# ctrl.net
KiCad netlist of a schematic drawn in EAGLE
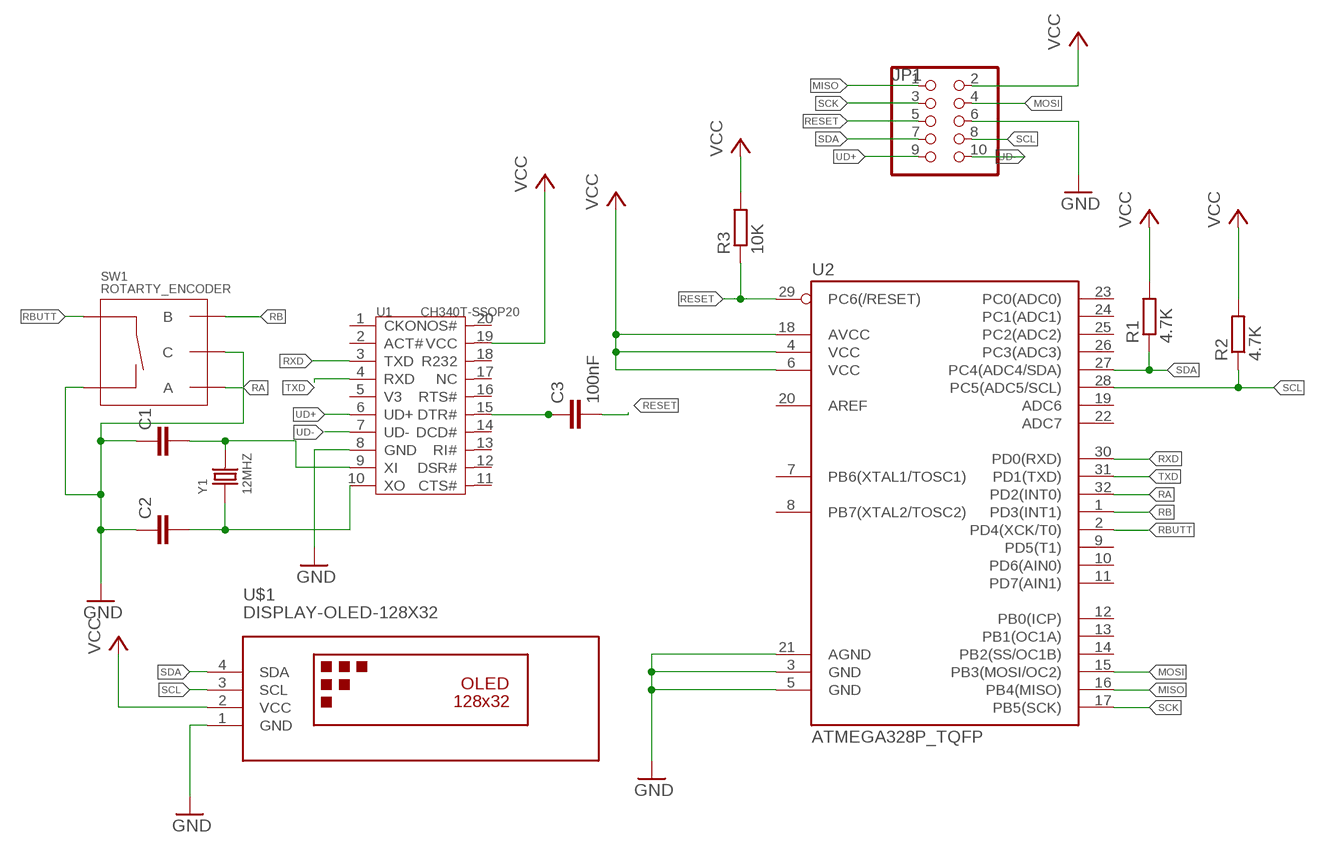
[diagram p0: schematic, sheet 1]

(export (version "E")
  (design (tool "Eeschema 10.0.6"))
  (components
    (comp (ref "C1")
      (value "C-EUC0805")
      (footprint "eagle-import:C0805")
      (libsource (lib "eagle-import") (part "C-EUC0805"))
    )
    (comp (ref "C2")
      (value "C-EUC0805")
      (footprint "eagle-import:C0805")
      (libsource (lib "eagle-import") (part "C-EUC0805"))
    )
    (comp (ref "C3")
      (value "100nF")
      (footprint "eagle-import:C0805")
      (libsource (lib "eagle-import") (part "C-EUC0805"))
    )
    (comp (ref "JP1")
      (value "PINHD-2X5")
      (footprint "eagle-import:2X05")
      (libsource (lib "eagle-import") (part "PINHD-2X5"))
    )
    (comp (ref "R1")
      (value "4.7K")
      (footprint "eagle-import:M0805")
      (libsource (lib "eagle-import") (part "R-EU_M0805"))
    )
    (comp (ref "R2")
      (value "4.7K")
      (footprint "eagle-import:M0805")
      (libsource (lib "eagle-import") (part "R-EU_M0805"))
    )
    (comp (ref "R3")
      (value "10K")
      (footprint "eagle-import:M0805")
      (libsource (lib "eagle-import") (part "R-EU_M0805"))
    )
    (comp (ref "SW1")
      (value "ROTARTY_ENCODER")
      (footprint "eagle-import:ROTARY_ENC_PLAIN")
      (libsource (lib "eagle-import") (part "ROTARTY_ENCODER"))
    )
    (comp (ref "U$1")
      (value "DISPLAY-OLED-128X32")
      (footprint "eagle-import:DISPLAY-OLED-128X32")
      (libsource (lib "eagle-import") (part "DISPLAY-OLED-128X32"))
    )
    (comp (ref "U1")
      (value "CH340T-SSOP20")
      (footprint "eagle-import:SSOP20-0.65-7.6X5.2MM")
      (fields (field (name "MPN") "CH340T"))
      (libsource (lib "eagle-import") (part "INTERFACE-CH340T(SSOP20)"))
    )
    (comp (ref "U2")
      (value "ATMEGA328P_TQFP")
      (footprint "eagle-import:TQFP32-08")
      (libsource (lib "eagle-import") (part "ATMEGA328P_TQFP"))
    )
    (comp (ref "Y1")
      (value "12MHZ")
      (footprint "eagle-import:X2-SMD-5.0X3.2X1.3MM")
      (fields (field (name "MPN") "5032/2P"))
      (libsource (lib "eagle-import") (part "SMD-CRYSTAL-12MHZ-20PF-20PPM-40R(2P-5.0X3.2MM)"))
    )
  )
  (nets
    (net (code "1") (name "/NOS#") (class "Default")
      (node (ref "U1") (pin "20") (pinfunction "NOS#_20") (pintype "power_in"))
    )
    (net (code "2") (name "/V3") (class "Default")
      (node (ref "U1") (pin "5") (pinfunction "V3_5") (pintype "power_in"))
    )
    (net (code "3") (name "GND") (class "Default")
      (node (ref "C1") (pin "1") (pinfunction "1_1") (pintype "passive"))
      (node (ref "C2") (pin "1") (pinfunction "1_1") (pintype "passive"))
      (node (ref "JP1") (pin "6") (pinfunction "6_6") (pintype "passive"))
      (node (ref "SW1") (pin "C") (pinfunction "C_C") (pintype "bidirectional"))
      (node (ref "SW1") (pin "SW-") (pinfunction "SW-_SW-") (pintype "bidirectional"))
      (node (ref "U$1") (pin "1") (pinfunction "GND_1") (pintype "power_in"))
      (node (ref "U1") (pin "8") (pinfunction "GND_8") (pintype "power_in"))
      (node (ref "U2") (pin "21") (pinfunction "AGND_21") (pintype "bidirectional"))
      (node (ref "U2") (pin "3") (pinfunction "GND_3") (pintype "bidirectional"))
      (node (ref "U2") (pin "5") (pinfunction "GND_5") (pintype "bidirectional"))
    )
    (net (code "4") (name "MISO") (class "Default")
      (node (ref "JP1") (pin "1") (pinfunction "1_1") (pintype "passive"))
      (node (ref "U2") (pin "16") (pinfunction "PB4(MISO)_16") (pintype "bidirectional"))
    )
    (net (code "5") (name "MOSI") (class "Default")
      (node (ref "JP1") (pin "4") (pinfunction "4_4") (pintype "passive"))
      (node (ref "U2") (pin "15") (pinfunction "PB3(MOSI/OC2)_15") (pintype "bidirectional"))
    )
    (net (code "6") (name "Net-(U1-DTR#)") (class "Default")
      (node (ref "C3") (pin "1") (pinfunction "1_1") (pintype "passive"))
      (node (ref "U1") (pin "15") (pinfunction "DTR#_15") (pintype "output"))
    )
    (net (code "7") (name "Net-(U1-XI)") (class "Default")
      (node (ref "C1") (pin "2") (pinfunction "2_2") (pintype "passive"))
      (node (ref "U1") (pin "9") (pinfunction "XI_9") (pintype "input"))
      (node (ref "Y1") (pin "2") (pinfunction "2_2") (pintype "passive"))
    )
    (net (code "8") (name "Net-(U1-XO)") (class "Default")
      (node (ref "C2") (pin "2") (pinfunction "2_2") (pintype "passive"))
      (node (ref "U1") (pin "10") (pinfunction "XO_10") (pintype "output"))
      (node (ref "Y1") (pin "1") (pinfunction "1_1") (pintype "passive"))
    )
    (net (code "9") (name "RA") (class "Default")
      (node (ref "SW1") (pin "A") (pinfunction "A_A") (pintype "bidirectional"))
      (node (ref "U2") (pin "32") (pinfunction "PD2(INT0)_32") (pintype "bidirectional"))
    )
    (net (code "10") (name "RB") (class "Default")
      (node (ref "SW1") (pin "B") (pinfunction "B_B") (pintype "bidirectional"))
      (node (ref "U2") (pin "1") (pinfunction "PD3(INT1)_1") (pintype "bidirectional"))
    )
    (net (code "11") (name "RBUTT") (class "Default")
      (node (ref "SW1") (pin "SW+") (pinfunction "SW+_SW+") (pintype "bidirectional"))
      (node (ref "U2") (pin "2") (pinfunction "PD4(XCK/T0)_2") (pintype "bidirectional"))
    )
    (net (code "12") (name "RESET") (class "Default")
      (node (ref "C3") (pin "2") (pinfunction "2_2") (pintype "passive"))
      (node (ref "JP1") (pin "5") (pinfunction "5_5") (pintype "passive"))
      (node (ref "R3") (pin "1") (pinfunction "1_1") (pintype "passive"))
      (node (ref "U2") (pin "29") (pinfunction "PC6(/RESET)_29") (pintype "bidirectional"))
    )
    (net (code "13") (name "RXD") (class "Default")
      (node (ref "U1") (pin "3") (pinfunction "TXD_3") (pintype "output"))
      (node (ref "U2") (pin "30") (pinfunction "PD0(RXD)_30") (pintype "bidirectional"))
    )
    (net (code "14") (name "SCK") (class "Default")
      (node (ref "JP1") (pin "3") (pinfunction "3_3") (pintype "passive"))
      (node (ref "U2") (pin "17") (pinfunction "PB5(SCK)_17") (pintype "bidirectional"))
    )
    (net (code "15") (name "SCL") (class "Default")
      (node (ref "JP1") (pin "8") (pinfunction "8_8") (pintype "passive"))
      (node (ref "R2") (pin "1") (pinfunction "1_1") (pintype "passive"))
      (node (ref "U$1") (pin "3") (pinfunction "SCL_3") (pintype "bidirectional"))
      (node (ref "U2") (pin "28") (pinfunction "PC5(ADC5/SCL)_28") (pintype "bidirectional"))
    )
    (net (code "16") (name "SDA") (class "Default")
      (node (ref "JP1") (pin "7") (pinfunction "7_7") (pintype "passive"))
      (node (ref "R1") (pin "1") (pinfunction "1_1") (pintype "passive"))
      (node (ref "U$1") (pin "4") (pinfunction "SDA_4") (pintype "bidirectional"))
      (node (ref "U2") (pin "27") (pinfunction "PC4(ADC4/SDA)_27") (pintype "bidirectional"))
    )
    (net (code "17") (name "TXD") (class "Default")
      (node (ref "U1") (pin "4") (pinfunction "RXD_4") (pintype "input"))
      (node (ref "U2") (pin "31") (pinfunction "PD1(TXD)_31") (pintype "bidirectional"))
    )
    (net (code "18") (name "UD+") (class "Default")
      (node (ref "JP1") (pin "9") (pinfunction "9_9") (pintype "passive"))
      (node (ref "U1") (pin "6") (pinfunction "UD+_6") (pintype "bidirectional"))
    )
    (net (code "19") (name "UD-") (class "Default")
      (node (ref "JP1") (pin "10") (pinfunction "10_10") (pintype "passive"))
      (node (ref "U1") (pin "7") (pinfunction "UD-_7") (pintype "bidirectional"))
    )
    (net (code "20") (name "VCC") (class "Default")
      (node (ref "JP1") (pin "2") (pinfunction "2_2") (pintype "passive"))
      (node (ref "R1") (pin "2") (pinfunction "2_2") (pintype "passive"))
      (node (ref "R2") (pin "2") (pinfunction "2_2") (pintype "passive"))
      (node (ref "R3") (pin "2") (pinfunction "2_2") (pintype "passive"))
      (node (ref "U$1") (pin "2") (pinfunction "VCC_2") (pintype "power_in"))
      (node (ref "U1") (pin "19") (pinfunction "VCC_19") (pintype "power_in"))
      (node (ref "U2") (pin "18") (pinfunction "AVCC_18") (pintype "bidirectional"))
      (node (ref "U2") (pin "4") (pinfunction "VCC_4") (pintype "bidirectional"))
      (node (ref "U2") (pin "6") (pinfunction "VCC_6") (pintype "bidirectional"))
    )
    (net (code "21") (name "unconnected-(U1-ACT#-Pad2)") (class "Default")
      (node (ref "U1") (pin "2") (pinfunction "ACT#_2") (pintype "output"))
    )
    (net (code "22") (name "unconnected-(U1-CKO-Pad1)") (class "Default")
      (node (ref "U1") (pin "1") (pinfunction "CKO_1") (pintype "output"))
    )
    (net (code "23") (name "unconnected-(U1-CTS#-Pad11)") (class "Default")
      (node (ref "U1") (pin "11") (pinfunction "CTS#_11") (pintype "input"))
    )
    (net (code "24") (name "unconnected-(U1-DCD#-Pad14)") (class "Default")
      (node (ref "U1") (pin "14") (pinfunction "DCD#_14") (pintype "input"))
    )
    (net (code "25") (name "unconnected-(U1-DSR#-Pad12)") (class "Default")
      (node (ref "U1") (pin "12") (pinfunction "DSR#_12") (pintype "input"))
    )
    (net (code "26") (name "unconnected-(U1-NC-Pad17)") (class "Default")
      (node (ref "U1") (pin "17") (pinfunction "NC_17") (pintype "no_connect"))
    )
    (net (code "27") (name "unconnected-(U1-R232-Pad18)") (class "Default")
      (node (ref "U1") (pin "18") (pinfunction "R232_18") (pintype "input"))
    )
    (net (code "28") (name "unconnected-(U1-RI#-Pad13)") (class "Default")
      (node (ref "U1") (pin "13") (pinfunction "RI#_13") (pintype "input"))
    )
    (net (code "29") (name "unconnected-(U1-RTS#-Pad16)") (class "Default")
      (node (ref "U1") (pin "16") (pinfunction "RTS#_16") (pintype "output"))
    )
    (net (code "30") (name "unconnected-(U2-ADC6-Pad19)") (class "Default")
      (node (ref "U2") (pin "19") (pinfunction "ADC6_19") (pintype "bidirectional"))
    )
    (net (code "31") (name "unconnected-(U2-ADC7-Pad22)") (class "Default")
      (node (ref "U2") (pin "22") (pinfunction "ADC7_22") (pintype "bidirectional"))
    )
    (net (code "32") (name "unconnected-(U2-AREF-Pad20)") (class "Default")
      (node (ref "U2") (pin "20") (pinfunction "AREF_20") (pintype "bidirectional"))
    )
    (net (code "33") (name "unconnected-(U2-PB0(ICP)-Pad12)") (class "Default")
      (node (ref "U2") (pin "12") (pinfunction "PB0(ICP)_12") (pintype "bidirectional"))
    )
    (net (code "34") (name "unconnected-(U2-PB1(OC1A)-Pad13)") (class "Default")
      (node (ref "U2") (pin "13") (pinfunction "PB1(OC1A)_13") (pintype "bidirectional"))
    )
    (net (code "35") (name "unconnected-(U2-PB2(SS{slash}OC1B)-Pad14)") (class "Default")
      (node (ref "U2") (pin "14") (pinfunction "PB2(SS/OC1B)_14") (pintype "bidirectional"))
    )
    (net (code "36") (name "unconnected-(U2-PB6(XTAL1{slash}TOSC1)-Pad7)") (class "Default")
      (node (ref "U2") (pin "7") (pinfunction "PB6(XTAL1/TOSC1)_7") (pintype "bidirectional"))
    )
    (net (code "37") (name "unconnected-(U2-PB7(XTAL2{slash}TOSC2)-Pad8)") (class "Default")
      (node (ref "U2") (pin "8") (pinfunction "PB7(XTAL2/TOSC2)_8") (pintype "bidirectional"))
    )
    (net (code "38") (name "unconnected-(U2-PC0(ADC0)-Pad23)") (class "Default")
      (node (ref "U2") (pin "23") (pinfunction "PC0(ADC0)_23") (pintype "bidirectional"))
    )
    (net (code "39") (name "unconnected-(U2-PC1(ADC1)-Pad24)") (class "Default")
      (node (ref "U2") (pin "24") (pinfunction "PC1(ADC1)_24") (pintype "bidirectional"))
    )
    (net (code "40") (name "unconnected-(U2-PC2(ADC2)-Pad25)") (class "Default")
      (node (ref "U2") (pin "25") (pinfunction "PC2(ADC2)_25") (pintype "bidirectional"))
    )
    (net (code "41") (name "unconnected-(U2-PC3(ADC3)-Pad26)") (class "Default")
      (node (ref "U2") (pin "26") (pinfunction "PC3(ADC3)_26") (pintype "bidirectional"))
    )
    (net (code "42") (name "unconnected-(U2-PD5(T1)-Pad9)") (class "Default")
      (node (ref "U2") (pin "9") (pinfunction "PD5(T1)_9") (pintype "bidirectional"))
    )
    (net (code "43") (name "unconnected-(U2-PD6(AIN0)-Pad10)") (class "Default")
      (node (ref "U2") (pin "10") (pinfunction "PD6(AIN0)_10") (pintype "bidirectional"))
    )
    (net (code "44") (name "unconnected-(U2-PD7(AIN1)-Pad11)") (class "Default")
      (node (ref "U2") (pin "11") (pinfunction "PD7(AIN1)_11") (pintype "bidirectional"))
    )
  )
)
